# OSSILEDControllerNew.net
KiCad netlist of a schematic drawn in EAGLE
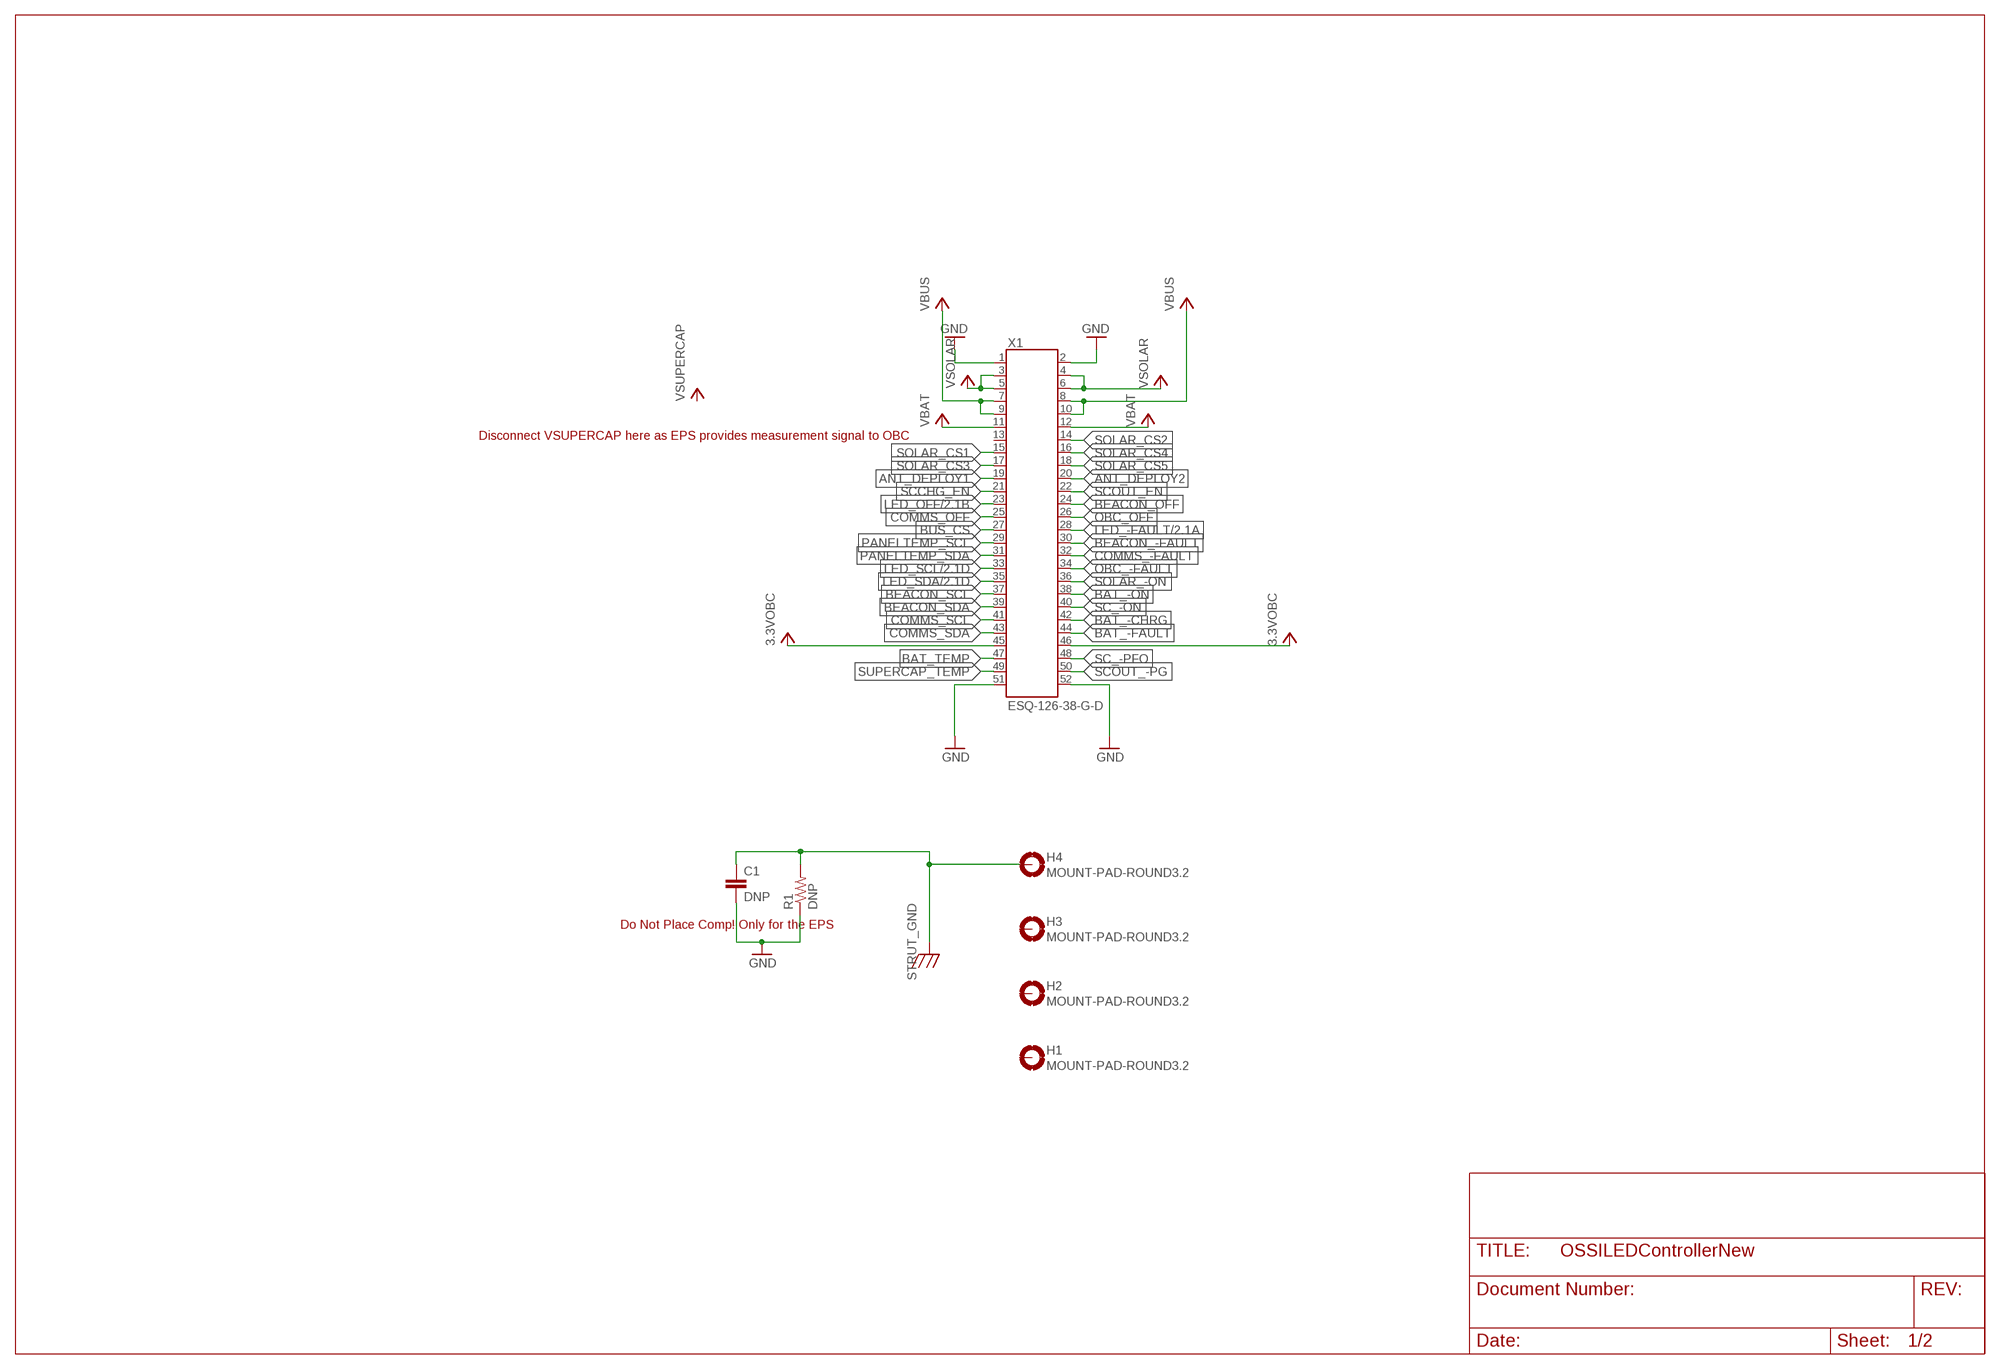
[diagram p0: schematic, sheet 1]
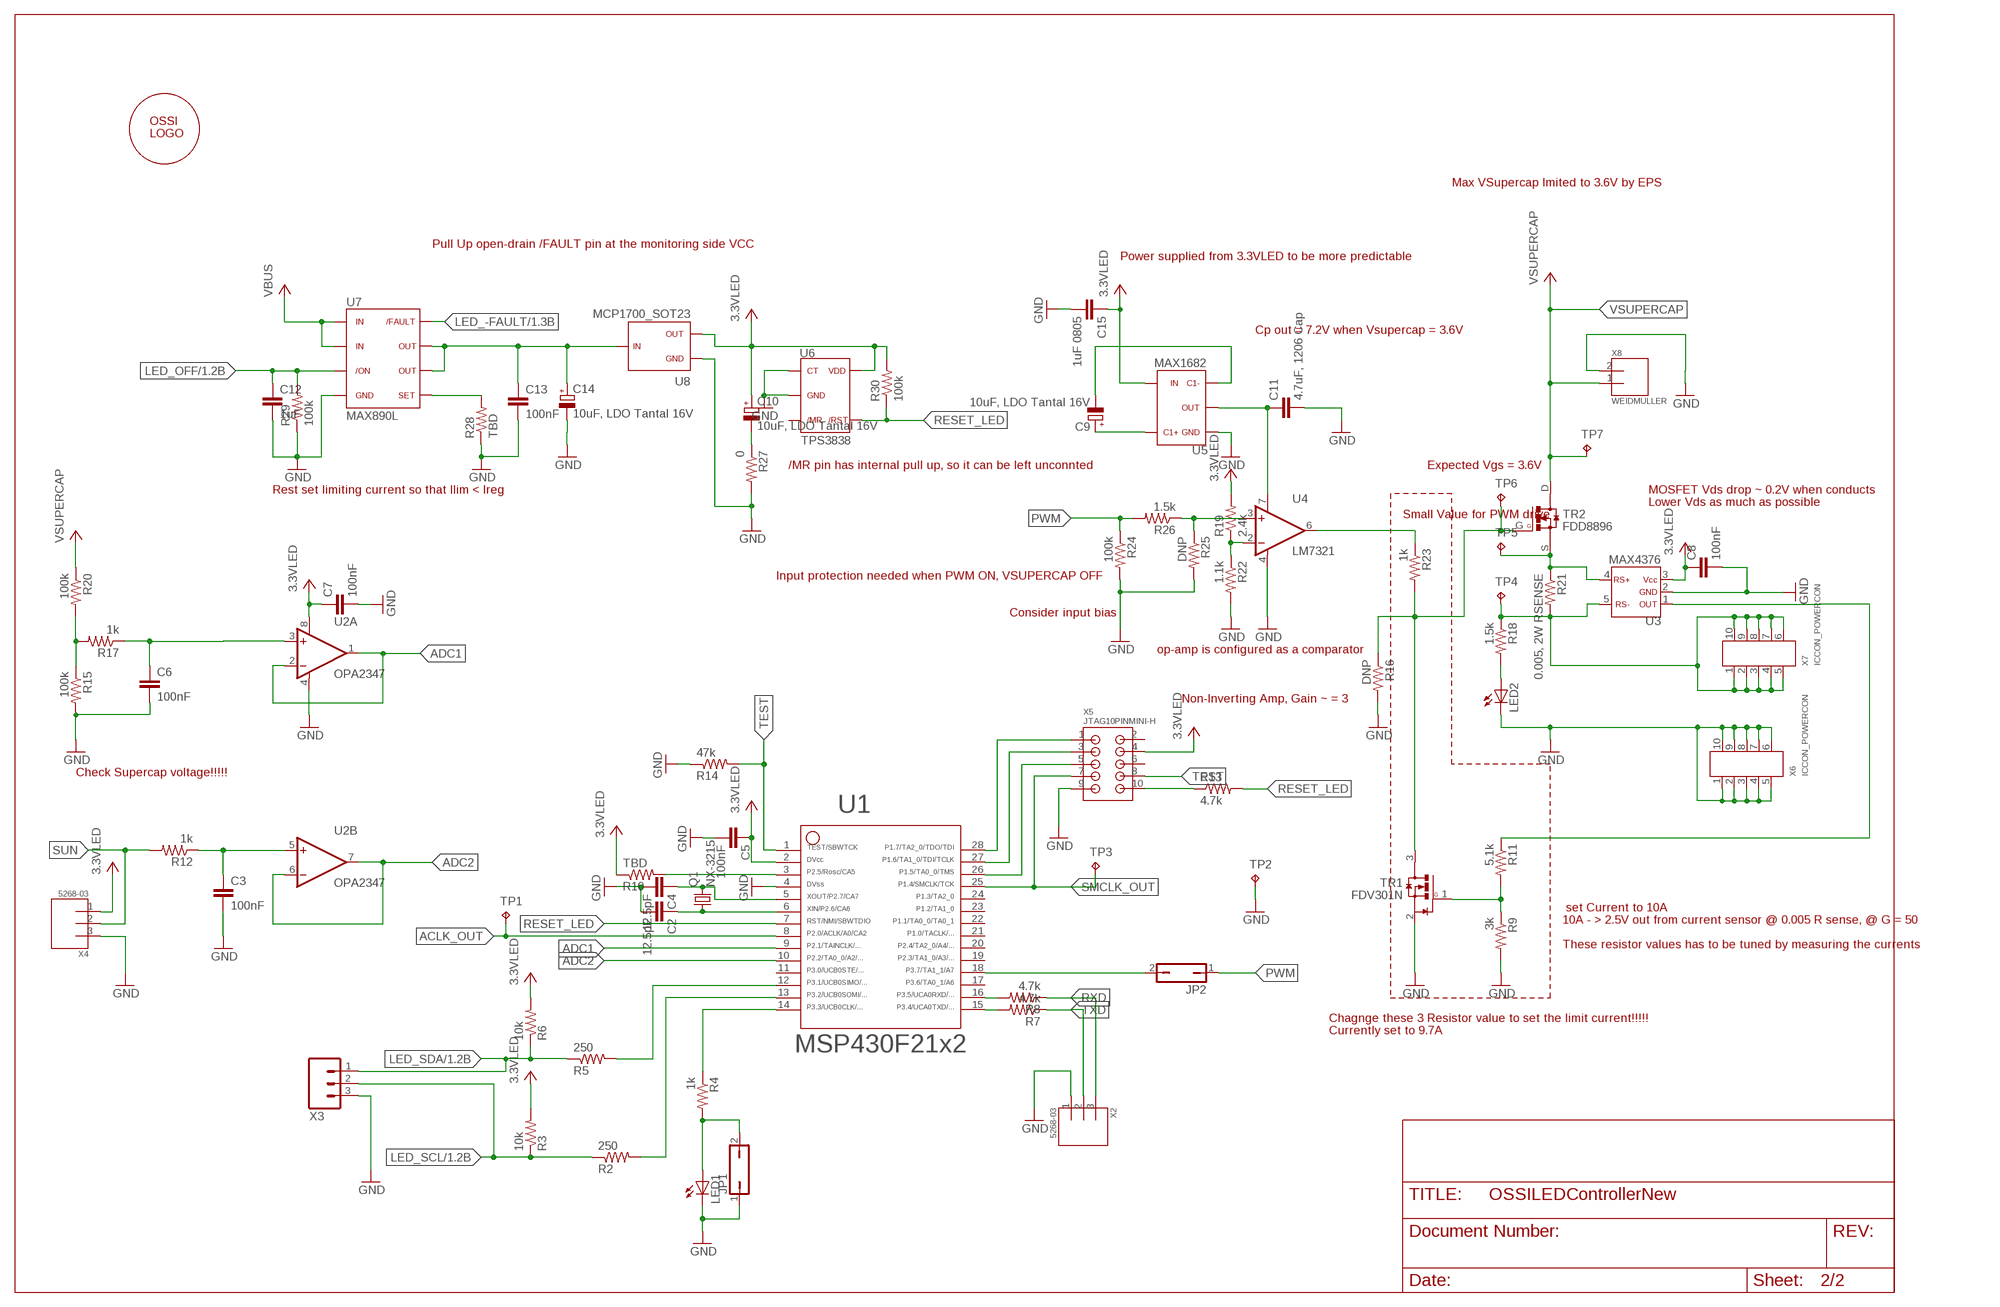
[diagram p1: schematic, sheet 2]

(export (version "E")
  (design (tool "Eeschema 10.0.6"))
  (components
    (comp (ref "C2")
      (value "12.5pF")
      (footprint "eagle-import:C0603(1608)")
      (libsource (lib "eagle-import") (part "C0603(1608)"))
    )
    (comp (ref "C3")
      (value "100nF")
      (footprint "eagle-import:C0603(1608)")
      (libsource (lib "eagle-import") (part "C0603(1608)"))
    )
    (comp (ref "C4")
      (value "12.5pF")
      (footprint "eagle-import:C0603(1608)")
      (libsource (lib "eagle-import") (part "C0603(1608)"))
    )
    (comp (ref "C5")
      (value "100nF")
      (footprint "eagle-import:C0603(1608)")
      (libsource (lib "eagle-import") (part "C0603(1608)"))
    )
    (comp (ref "C6")
      (value "100nF")
      (footprint "eagle-import:C0603(1608)")
      (libsource (lib "eagle-import") (part "C0603(1608)"))
    )
    (comp (ref "C7")
      (value "100nF")
      (footprint "eagle-import:C0603(1608)")
      (libsource (lib "eagle-import") (part "C0603(1608)"))
    )
    (comp (ref "C8")
      (value "100nF")
      (footprint "eagle-import:C0603(1608)")
      (libsource (lib "eagle-import") (part "C0603(1608)"))
    )
    (comp (ref "C9")
      (value "10uF, LDO Tantal 16V")
      (footprint "eagle-import:C1206(3216)-A")
      (libsource (lib "eagle-import") (part "C-TANTAL-A"))
    )
    (comp (ref "C10")
      (value "10uF, LDO Tantal 16V")
      (footprint "eagle-import:C1206(3216)-A")
      (libsource (lib "eagle-import") (part "C-TANTAL-A"))
    )
    (comp (ref "C11")
      (value "4.7uF, 1206 Cap")
      (footprint "eagle-import:C1206-GCM31")
      (libsource (lib "eagle-import") (part "C1206(3216)-GCM31"))
    )
    (comp (ref "C12")
      (value "1uF")
      (footprint "eagle-import:C0603(1608)")
      (libsource (lib "eagle-import") (part "C0603(1608)"))
    )
    (comp (ref "C13")
      (value "100nF")
      (footprint "eagle-import:C0603(1608)")
      (libsource (lib "eagle-import") (part "C0603(1608)"))
    )
    (comp (ref "C14")
      (value "10uF, LDO Tantal 16V")
      (footprint "eagle-import:C1206(3216)-A")
      (libsource (lib "eagle-import") (part "C-TANTAL-A"))
    )
    (comp (ref "C15")
      (value "1uF 0805")
      (footprint "eagle-import:C0805(2012)")
      (libsource (lib "eagle-import") (part "C0805(2012)"))
    )
    (comp (ref "JP1")
      (value "JP1Q")
      (footprint "eagle-import:JP1")
      (libsource (lib "eagle-import") (part "JP1Q"))
    )
    (comp (ref "JP2")
      (value "JP1Q")
      (footprint "eagle-import:JP1")
      (libsource (lib "eagle-import") (part "JP1Q"))
    )
    (comp (ref "LED1")
      (value "LED0603")
      (footprint "eagle-import:LED-0603")
      (libsource (lib "eagle-import") (part "LED0603"))
    )
    (comp (ref "LED2")
      (value "LEDCHIPLED_0603")
      (footprint "eagle-import:CHIPLED_0603")
      (libsource (lib "eagle-import") (part "LEDCHIPLED_0603"))
    )
    (comp (ref "Q1")
      (value "NX-3215")
      (footprint "eagle-import:NX-3215")
      (libsource (lib "eagle-import") (part "NX-3215"))
    )
    (comp (ref "R2")
      (value "250")
      (footprint "eagle-import:R0603(1608)")
      (libsource (lib "eagle-import") (part "R0603(1608)"))
    )
    (comp (ref "R3")
      (value "10k")
      (footprint "eagle-import:R0603(1608)")
      (libsource (lib "eagle-import") (part "R0603(1608)"))
    )
    (comp (ref "R4")
      (value "1k")
      (footprint "eagle-import:R0603(1608)")
      (libsource (lib "eagle-import") (part "R0603(1608)"))
    )
    (comp (ref "R5")
      (value "250")
      (footprint "eagle-import:R0603(1608)")
      (libsource (lib "eagle-import") (part "R0603(1608)"))
    )
    (comp (ref "R6")
      (value "10k")
      (footprint "eagle-import:R0603(1608)")
      (libsource (lib "eagle-import") (part "R0603(1608)"))
    )
    (comp (ref "R7")
      (value "4.7k")
      (footprint "eagle-import:R0603(1608)")
      (libsource (lib "eagle-import") (part "R0603(1608)"))
    )
    (comp (ref "R8")
      (value "4.7k")
      (footprint "eagle-import:R0603(1608)")
      (libsource (lib "eagle-import") (part "R0603(1608)"))
    )
    (comp (ref "R9")
      (value "3k")
      (footprint "eagle-import:R0603(1608)")
      (libsource (lib "eagle-import") (part "R0603(1608)"))
    )
    (comp (ref "R10")
      (value "TBD")
      (footprint "eagle-import:R0603(1608)")
      (libsource (lib "eagle-import") (part "R0603(1608)"))
    )
    (comp (ref "R11")
      (value "5.1k")
      (footprint "eagle-import:R0603(1608)")
      (libsource (lib "eagle-import") (part "R0603(1608)"))
    )
    (comp (ref "R12")
      (value "1k")
      (footprint "eagle-import:R0603(1608)")
      (libsource (lib "eagle-import") (part "R0603(1608)"))
    )
    (comp (ref "R13")
      (value "4.7k")
      (footprint "eagle-import:R0603(1608)")
      (libsource (lib "eagle-import") (part "R0603(1608)"))
    )
    (comp (ref "R14")
      (value "47k")
      (footprint "eagle-import:R0603(1608)")
      (libsource (lib "eagle-import") (part "R0603(1608)"))
    )
    (comp (ref "R15")
      (value "100k")
      (footprint "eagle-import:R0603(1608)")
      (libsource (lib "eagle-import") (part "R0603(1608)"))
    )
    (comp (ref "R16")
      (value "DNP")
      (footprint "eagle-import:R0603(1608)")
      (libsource (lib "eagle-import") (part "R0603(1608)"))
    )
    (comp (ref "R17")
      (value "1k")
      (footprint "eagle-import:R0603(1608)")
      (libsource (lib "eagle-import") (part "R0603(1608)"))
    )
    (comp (ref "R18")
      (value "1.5k")
      (footprint "eagle-import:R0603(1608)")
      (libsource (lib "eagle-import") (part "R0603(1608)"))
    )
    (comp (ref "R19")
      (value "2.4k")
      (footprint "eagle-import:R0603(1608)")
      (libsource (lib "eagle-import") (part "R0603(1608)"))
    )
    (comp (ref "R20")
      (value "100k")
      (footprint "eagle-import:R0603(1608)")
      (libsource (lib "eagle-import") (part "R0603(1608)"))
    )
    (comp (ref "R21")
      (value "0.005, 2W RSENSE")
      (footprint "eagle-import:R4527(12070)")
      (libsource (lib "eagle-import") (part "RWSR2"))
    )
    (comp (ref "R22")
      (value "1.1k")
      (footprint "eagle-import:R0603(1608)")
      (libsource (lib "eagle-import") (part "R0603(1608)"))
    )
    (comp (ref "R23")
      (value "1k")
      (footprint "eagle-import:R0603(1608)")
      (libsource (lib "eagle-import") (part "R0603(1608)"))
    )
    (comp (ref "R24")
      (value "100k")
      (footprint "eagle-import:R0603(1608)")
      (libsource (lib "eagle-import") (part "R0603(1608)"))
    )
    (comp (ref "R25")
      (value "DNP")
      (footprint "eagle-import:R0603(1608)")
      (libsource (lib "eagle-import") (part "R0603(1608)"))
    )
    (comp (ref "R26")
      (value "1.5k")
      (footprint "eagle-import:R0603(1608)")
      (libsource (lib "eagle-import") (part "R0603(1608)"))
    )
    (comp (ref "R27")
      (value "0")
      (footprint "eagle-import:R0603(1608)")
      (libsource (lib "eagle-import") (part "R0603(1608)"))
    )
    (comp (ref "R28")
      (value "TBD")
      (footprint "eagle-import:R0603(1608)")
      (libsource (lib "eagle-import") (part "R0603(1608)"))
    )
    (comp (ref "R29")
      (value "100k")
      (footprint "eagle-import:R0603(1608)")
      (libsource (lib "eagle-import") (part "R0603(1608)"))
    )
    (comp (ref "R30")
      (value "100k")
      (footprint "eagle-import:R0603(1608)")
      (libsource (lib "eagle-import") (part "R0603(1608)"))
    )
    (comp (ref "TP1")
      (value "TP")
      (footprint "eagle-import:TP-13")
      (libsource (lib "eagle-import") (part "TP"))
    )
    (comp (ref "TP2")
      (value "TP")
      (footprint "eagle-import:TP-13")
      (libsource (lib "eagle-import") (part "TP"))
    )
    (comp (ref "TP3")
      (value "TP")
      (footprint "eagle-import:TP-13")
      (libsource (lib "eagle-import") (part "TP"))
    )
    (comp (ref "TP4")
      (value "TP")
      (footprint "eagle-import:TP-13")
      (libsource (lib "eagle-import") (part "TP"))
    )
    (comp (ref "TP5")
      (value "TP")
      (footprint "eagle-import:TP-13")
      (libsource (lib "eagle-import") (part "TP"))
    )
    (comp (ref "TP6")
      (value "TP")
      (footprint "eagle-import:TP-13")
      (libsource (lib "eagle-import") (part "TP"))
    )
    (comp (ref "TP7")
      (value "TP")
      (footprint "eagle-import:TP-13")
      (libsource (lib "eagle-import") (part "TP"))
    )
    (comp (ref "TR1")
      (value "FDV301N")
      (footprint "eagle-import:SOT23")
      (libsource (lib "eagle-import") (part "FDV301N"))
    )
    (comp (ref "TR2")
      (value "FDD8896")
      (footprint "eagle-import:TO252")
      (libsource (lib "eagle-import") (part "FDD8896"))
    )
    (comp (ref "U$")
      (value "OSSILOGORECT")
      (footprint "eagle-import:OSSILOGORECT1005")
      (libsource (lib "eagle-import") (part "OSSILOGORECT"))
    )
    (comp (ref "U1")
      (value "MSP430F2132")
      (footprint "eagle-import:PW28")
      (libsource (lib "eagle-import") (part "MSP430F2132"))
    )
    (comp (ref "U2")
      (value "OPA2347")
      (footprint "eagle-import:SOT23-8DCN")
      (libsource (lib "eagle-import") (part "OPA2347"))
    )
    (comp (ref "U3")
      (value "MAX4376")
      (footprint "eagle-import:SOT23-5DBV")
      (libsource (lib "eagle-import") (part "MAX4376"))
    )
    (comp (ref "U4")
      (value "LM7321")
      (footprint "eagle-import:SO8")
      (libsource (lib "eagle-import") (part "LM7321"))
    )
    (comp (ref "U5")
      (value "MAX1682")
      (footprint "eagle-import:SOT23-5DBV")
      (libsource (lib "eagle-import") (part "MAX1682"))
    )
    (comp (ref "U6")
      (value "TPS3838")
      (footprint "eagle-import:SOT23-5DBV")
      (libsource (lib "eagle-import") (part "TPS3838"))
    )
    (comp (ref "U7")
      (value "MAX890L")
      (footprint "eagle-import:SO8")
      (libsource (lib "eagle-import") (part "MAX890L"))
    )
    (comp (ref "U8")
      (value "MCP1700_SOT23")
      (footprint "eagle-import:SOT23")
      (libsource (lib "eagle-import") (part "MCP1700_SOT23"))
    )
    (comp (ref "X2")
      (value "5268-03")
      (footprint "eagle-import:5268-03")
      (libsource (lib "eagle-import") (part "5268-03"))
    )
    (comp (ref "X3")
      (value "M03PTH")
      (footprint "eagle-import:1X03")
      (libsource (lib "eagle-import") (part "M03PTH"))
    )
    (comp (ref "X4")
      (value "5268-03")
      (footprint "eagle-import:5268-03")
      (libsource (lib "eagle-import") (part "5268-03"))
    )
    (comp (ref "X5")
      (value "JTAG10PINMINI-H")
      (footprint "eagle-import:M50-3200545")
      (libsource (lib "eagle-import") (part "JTAG10PINMINI-H"))
    )
    (comp (ref "X6")
      (value "ICCON_POWERCON")
      (footprint "eagle-import:ICCON6643220-1")
      (libsource (lib "eagle-import") (part "ICCON_POWERCON"))
    )
    (comp (ref "X7")
      (value "ICCON_POWERCON")
      (footprint "eagle-import:ICCON6643220-1")
      (libsource (lib "eagle-import") (part "ICCON_POWERCON"))
    )
    (comp (ref "X8")
      (value "WEIDMULLER")
      (footprint "eagle-import:WEIDMULLER1760490000")
      (libsource (lib "eagle-import") (part "WEIDMULLER"))
    )
    (comp (ref "C1")
      (value "DNP")
      (footprint "eagle-import:C0805(2012)")
      (libsource (lib "eagle-import") (part "C0805(2012)"))
    )
    (comp (ref "H1")
      (value "MOUNT-PAD-ROUND3.2")
      (footprint "eagle-import:3.2-PAD-ROUND")
      (libsource (lib "eagle-import") (part "MOUNT-PAD-ROUND3.2"))
    )
    (comp (ref "H2")
      (value "MOUNT-PAD-ROUND3.2")
      (footprint "eagle-import:3.2-PAD-ROUND")
      (libsource (lib "eagle-import") (part "MOUNT-PAD-ROUND3.2"))
    )
    (comp (ref "H3")
      (value "MOUNT-PAD-ROUND3.2")
      (footprint "eagle-import:3.2-PAD-ROUND")
      (libsource (lib "eagle-import") (part "MOUNT-PAD-ROUND3.2"))
    )
    (comp (ref "H4")
      (value "MOUNT-PAD-ROUND3.2")
      (footprint "eagle-import:3.2-PAD-ROUND")
      (libsource (lib "eagle-import") (part "MOUNT-PAD-ROUND3.2"))
    )
    (comp (ref "R1")
      (value "DNP")
      (footprint "eagle-import:WSL1206")
      (libsource (lib "eagle-import") (part "RWSL1206"))
    )
    (comp (ref "X1")
      (value "ESQ-126-38-G-D")
      (footprint "eagle-import:ESQ-126-XX-X-D")
      (libsource (lib "eagle-import") (part "ESQ-126-38-G-D"))
    )
  )
  (nets
    (net (code "1") (name "3.3VLED") (class "Default")
      (node (ref "C10") (pin "1") (pinfunction "+_1") (pintype "passive"))
      (node (ref "C15") (pin "1") (pinfunction "1_1") (pintype "passive"))
      (node (ref "C5") (pin "1") (pinfunction "1_1") (pintype "passive"))
      (node (ref "C7") (pin "1") (pinfunction "1_1") (pintype "passive"))
      (node (ref "C8") (pin "1") (pinfunction "1_1") (pintype "passive"))
      (node (ref "R10") (pin "1") (pinfunction "1_1") (pintype "passive"))
      (node (ref "R19") (pin "2") (pinfunction "2_2") (pintype "passive"))
      (node (ref "R3") (pin "2") (pinfunction "2_2") (pintype "passive"))
      (node (ref "R30") (pin "2") (pinfunction "2_2") (pintype "passive"))
      (node (ref "R6") (pin "2") (pinfunction "2_2") (pintype "passive"))
      (node (ref "U1") (pin "2") (pinfunction "2_2") (pintype "power_in"))
      (node (ref "U2") (pin "8") (pinfunction "V+_8") (pintype "power_in"))
      (node (ref "U3") (pin "3") (pinfunction "P$3_3") (pintype "power_in"))
      (node (ref "U5") (pin "4") (pinfunction "P$4_4") (pintype "power_in"))
      (node (ref "U6") (pin "5") (pinfunction "P$5_5") (pintype "power_in"))
      (node (ref "U8") (pin "2") (pinfunction "2_2") (pintype "power_in"))
      (node (ref "X4") (pin "1") (pinfunction "1_1") (pintype "bidirectional"))
      (node (ref "X5") (pin "4") (pinfunction "4_4") (pintype "bidirectional"))
    )
    (net (code "2") (name "3.3VOBC") (class "Default")
      (node (ref "X1") (pin "45") (pinfunction "45_45") (pintype "bidirectional"))
      (node (ref "X1") (pin "46") (pinfunction "46_46") (pintype "bidirectional"))
    )
    (net (code "3") (name "ACLK_OUT") (class "Default")
      (node (ref "TP1") (pin "TP") (pinfunction "TP_TP") (pintype "input"))
      (node (ref "U1") (pin "8") (pinfunction "8_8") (pintype "bidirectional"))
    )
    (net (code "4") (name "ADC1") (class "Default")
      (node (ref "U1") (pin "9") (pinfunction "9_9") (pintype "bidirectional"))
      (node (ref "U2") (pin "1") (pinfunction "OUT_1") (pintype "output"))
      (node (ref "U2") (pin "2") (pinfunction "-IN_2") (pintype "input"))
    )
    (net (code "5") (name "ADC2") (class "Default")
      (node (ref "U1") (pin "10") (pinfunction "10_10") (pintype "bidirectional"))
      (node (ref "U2") (pin "6") (pinfunction "-IN_6") (pintype "input"))
      (node (ref "U2") (pin "7") (pinfunction "OUT_7") (pintype "output"))
    )
    (net (code "6") (name "ANT_DEPLOY1") (class "Default")
      (node (ref "X1") (pin "19") (pinfunction "19_19") (pintype "bidirectional"))
    )
    (net (code "7") (name "ANT_DEPLOY2") (class "Default")
      (node (ref "X1") (pin "20") (pinfunction "20_20") (pintype "bidirectional"))
    )
    (net (code "8") (name "BAT_-CHRG") (class "Default")
      (node (ref "X1") (pin "42") (pinfunction "42_42") (pintype "bidirectional"))
    )
    (net (code "9") (name "BAT_-FAULT") (class "Default")
      (node (ref "X1") (pin "44") (pinfunction "44_44") (pintype "bidirectional"))
    )
    (net (code "10") (name "BAT_-ON") (class "Default")
      (node (ref "X1") (pin "38") (pinfunction "38_38") (pintype "bidirectional"))
    )
    (net (code "11") (name "BAT_TEMP") (class "Default")
      (node (ref "X1") (pin "47") (pinfunction "47_47") (pintype "bidirectional"))
    )
    (net (code "12") (name "BEACON_-FAULT") (class "Default")
      (node (ref "X1") (pin "30") (pinfunction "30_30") (pintype "bidirectional"))
    )
    (net (code "13") (name "BEACON_OFF") (class "Default")
      (node (ref "X1") (pin "24") (pinfunction "24_24") (pintype "bidirectional"))
    )
    (net (code "14") (name "BEACON_SCL") (class "Default")
      (node (ref "X1") (pin "37") (pinfunction "37_37") (pintype "bidirectional"))
    )
    (net (code "15") (name "BEACON_SDA") (class "Default")
      (node (ref "X1") (pin "39") (pinfunction "39_39") (pintype "bidirectional"))
    )
    (net (code "16") (name "BUS_CS") (class "Default")
      (node (ref "X1") (pin "27") (pinfunction "27_27") (pintype "bidirectional"))
    )
    (net (code "17") (name "COMMS_-FAULT") (class "Default")
      (node (ref "X1") (pin "32") (pinfunction "32_32") (pintype "bidirectional"))
    )
    (net (code "18") (name "COMMS_OFF") (class "Default")
      (node (ref "X1") (pin "25") (pinfunction "25_25") (pintype "bidirectional"))
    )
    (net (code "19") (name "COMMS_SCL") (class "Default")
      (node (ref "X1") (pin "41") (pinfunction "41_41") (pintype "bidirectional"))
    )
    (net (code "20") (name "COMMS_SDA") (class "Default")
      (node (ref "X1") (pin "43") (pinfunction "43_43") (pintype "bidirectional"))
    )
    (net (code "21") (name "GND") (class "Default")
      (node (ref "C1") (pin "2") (pinfunction "2_2") (pintype "passive"))
      (node (ref "C11") (pin "P$2") (pinfunction "2_P$2") (pintype "passive"))
      (node (ref "C12") (pin "2") (pinfunction "2_2") (pintype "passive"))
      (node (ref "C13") (pin "2") (pinfunction "2_2") (pintype "passive"))
      (node (ref "C14") (pin "2") (pinfunction "-_2") (pintype "passive"))
      (node (ref "C15") (pin "2") (pinfunction "2_2") (pintype "passive"))
      (node (ref "C2") (pin "2") (pinfunction "2_2") (pintype "passive"))
      (node (ref "C3") (pin "2") (pinfunction "2_2") (pintype "passive"))
      (node (ref "C4") (pin "2") (pinfunction "2_2") (pintype "passive"))
      (node (ref "C5") (pin "2") (pinfunction "2_2") (pintype "passive"))
      (node (ref "C6") (pin "2") (pinfunction "2_2") (pintype "passive"))
      (node (ref "C7") (pin "2") (pinfunction "2_2") (pintype "passive"))
      (node (ref "C8") (pin "2") (pinfunction "2_2") (pintype "passive"))
      (node (ref "JP1") (pin "1") (pinfunction "1_1") (pintype "passive"))
      (node (ref "LED1") (pin "C") (pinfunction "C_C") (pintype "passive"))
      (node (ref "LED2") (pin "C") (pinfunction "C_C") (pintype "passive"))
      (node (ref "R1") (pin "P$1") (pinfunction "1_P$1") (pintype "passive"))
      (node (ref "R14") (pin "1") (pinfunction "1_1") (pintype "passive"))
      (node (ref "R15") (pin "2") (pinfunction "2_2") (pintype "passive"))
      (node (ref "R16") (pin "2") (pinfunction "2_2") (pintype "passive"))
      (node (ref "R22") (pin "2") (pinfunction "2_2") (pintype "passive"))
      (node (ref "R24") (pin "2") (pinfunction "2_2") (pintype "passive"))
      (node (ref "R25") (pin "2") (pinfunction "2_2") (pintype "passive"))
      (node (ref "R27") (pin "2") (pinfunction "2_2") (pintype "passive"))
      (node (ref "R28") (pin "1") (pinfunction "1_1") (pintype "passive"))
      (node (ref "R29") (pin "1") (pinfunction "1_1") (pintype "passive"))
      (node (ref "R9") (pin "2") (pinfunction "2_2") (pintype "passive"))
      (node (ref "TP2") (pin "TP") (pinfunction "TP_TP") (pintype "input"))
      (node (ref "TR1") (pin "2") (pinfunction "S_2") (pintype "bidirectional"))
      (node (ref "U1") (pin "4") (pinfunction "4_4") (pintype "power_in"))
      (node (ref "U2") (pin "4") (pinfunction "V-_4") (pintype "power_in"))
      (node (ref "U3") (pin "2") (pinfunction "P$2_2") (pintype "power_in"))
      (node (ref "U4") (pin "4") (pinfunction "V-_4") (pintype "power_in"))
      (node (ref "U5") (pin "1") (pinfunction "P$1_1") (pintype "power_in"))
      (node (ref "U6") (pin "1") (pinfunction "P$1_1") (pintype "bidirectional"))
      (node (ref "U6") (pin "2") (pinfunction "P$2_2") (pintype "power_in"))
      (node (ref "U7") (pin "4") (pinfunction "P$4_4") (pintype "power_in"))
      (node (ref "U8") (pin "1") (pinfunction "1_1") (pintype "power_in"))
      (node (ref "X1") (pin "1") (pinfunction "1_1") (pintype "bidirectional"))
      (node (ref "X1") (pin "2") (pinfunction "2_2") (pintype "bidirectional"))
      (node (ref "X1") (pin "51") (pinfunction "51_51") (pintype "bidirectional"))
      (node (ref "X1") (pin "52") (pinfunction "52_52") (pintype "bidirectional"))
      (node (ref "X2") (pin "1") (pinfunction "1_1") (pintype "bidirectional"))
      (node (ref "X3") (pin "3") (pinfunction "3_3") (pintype "passive"))
      (node (ref "X4") (pin "3") (pinfunction "3_3") (pintype "bidirectional"))
      (node (ref "X5") (pin "9") (pinfunction "9_9") (pintype "bidirectional"))
      (node (ref "X6") (pin "1") (pinfunction "P$1_1") (pintype "bidirectional"))
      (node (ref "X6") (pin "10") (pinfunction "P$10_10") (pintype "bidirectional"))
      (node (ref "X6") (pin "2") (pinfunction "P$2_2") (pintype "bidirectional"))
      (node (ref "X6") (pin "3") (pinfunction "P$3_3") (pintype "bidirectional"))
      (node (ref "X6") (pin "4") (pinfunction "P$4_4") (pintype "bidirectional"))
      (node (ref "X6") (pin "5") (pinfunction "P$5_5") (pintype "bidirectional"))
      (node (ref "X6") (pin "6") (pinfunction "P$6_6") (pintype "bidirectional"))
      (node (ref "X6") (pin "7") (pinfunction "P$7_7") (pintype "bidirectional"))
      (node (ref "X6") (pin "8") (pinfunction "P$8_8") (pintype "bidirectional"))
      (node (ref "X6") (pin "9") (pinfunction "P$9_9") (pintype "bidirectional"))
      (node (ref "X8") (pin "2") (pinfunction "2_2") (pintype "bidirectional"))
    )
    (net (code "22") (name "LED_-FAULT") (class "Default")
      (node (ref "U7") (pin "8") (pinfunction "P$8_8") (pintype "output"))
      (node (ref "X1") (pin "28") (pinfunction "28_28") (pintype "bidirectional"))
    )
    (net (code "23") (name "LED_OFF") (class "Default")
      (node (ref "C12") (pin "1") (pinfunction "1_1") (pintype "passive"))
      (node (ref "R29") (pin "2") (pinfunction "2_2") (pintype "passive"))
      (node (ref "U7") (pin "3") (pinfunction "P$3_3") (pintype "input"))
      (node (ref "X1") (pin "23") (pinfunction "23_23") (pintype "bidirectional"))
    )
    (net (code "24") (name "LED_SCL") (class "Default")
      (node (ref "R2") (pin "1") (pinfunction "1_1") (pintype "passive"))
      (node (ref "R3") (pin "1") (pinfunction "1_1") (pintype "passive"))
      (node (ref "X1") (pin "33") (pinfunction "33_33") (pintype "bidirectional"))
      (node (ref "X3") (pin "2") (pinfunction "2_2") (pintype "passive"))
    )
    (net (code "25") (name "LED_SDA") (class "Default")
      (node (ref "R5") (pin "1") (pinfunction "1_1") (pintype "passive"))
      (node (ref "R6") (pin "1") (pinfunction "1_1") (pintype "passive"))
      (node (ref "X1") (pin "35") (pinfunction "35_35") (pintype "bidirectional"))
      (node (ref "X3") (pin "1") (pinfunction "1_1") (pintype "passive"))
    )
    (net (code "26") (name "Net-(C2-Pad1)") (class "Default")
      (node (ref "C2") (pin "1") (pinfunction "1_1") (pintype "passive"))
      (node (ref "Q1") (pin "1") (pinfunction "1_1") (pintype "passive"))
      (node (ref "U1") (pin "6") (pinfunction "6_6") (pintype "bidirectional"))
    )
    (net (code "27") (name "Net-(C4-Pad1)") (class "Default")
      (node (ref "C4") (pin "1") (pinfunction "1_1") (pintype "passive"))
      (node (ref "Q1") (pin "2") (pinfunction "2_2") (pintype "passive"))
      (node (ref "U1") (pin "5") (pinfunction "5_5") (pintype "bidirectional"))
    )
    (net (code "28") (name "Net-(C9-+)") (class "Default")
      (node (ref "C9") (pin "1") (pinfunction "+_1") (pintype "passive"))
      (node (ref "U5") (pin "5") (pinfunction "P$5_5") (pintype "passive"))
    )
    (net (code "29") (name "Net-(C9--)") (class "Default")
      (node (ref "C9") (pin "2") (pinfunction "-_2") (pintype "passive"))
      (node (ref "U5") (pin "3") (pinfunction "P$3_3") (pintype "passive"))
    )
    (net (code "30") (name "Net-(C10--)") (class "Default")
      (node (ref "C10") (pin "2") (pinfunction "-_2") (pintype "passive"))
      (node (ref "R27") (pin "1") (pinfunction "1_1") (pintype "passive"))
    )
    (net (code "31") (name "Net-(C11-1)") (class "Default")
      (node (ref "C11") (pin "P$1") (pinfunction "1_P$1") (pintype "passive"))
      (node (ref "U4") (pin "7") (pinfunction "V+_7") (pintype "power_in"))
      (node (ref "U5") (pin "2") (pinfunction "P$2_2") (pintype "power_in"))
    )
    (net (code "32") (name "Net-(C14-+)") (class "Default")
      (node (ref "C13") (pin "1") (pinfunction "1_1") (pintype "passive"))
      (node (ref "C14") (pin "1") (pinfunction "+_1") (pintype "passive"))
      (node (ref "U7") (pin "6") (pinfunction "P$6_6") (pintype "output"))
      (node (ref "U7") (pin "7") (pinfunction "P$7_7") (pintype "output"))
      (node (ref "U8") (pin "3") (pinfunction "3_3") (pintype "power_in"))
    )
    (net (code "33") (name "Net-(JP1-Pad2)") (class "Default")
      (node (ref "JP1") (pin "2") (pinfunction "2_2") (pintype "passive"))
      (node (ref "LED1") (pin "A") (pinfunction "A_A") (pintype "passive"))
      (node (ref "R4") (pin "2") (pinfunction "2_2") (pintype "passive"))
    )
    (net (code "34") (name "Net-(JP2-Pad2)") (class "Default")
      (node (ref "JP2") (pin "2") (pinfunction "2_2") (pintype "passive"))
      (node (ref "U1") (pin "18") (pinfunction "18_18") (pintype "bidirectional"))
    )
    (net (code "35") (name "Net-(LED2-PadA)") (class "Default")
      (node (ref "LED2") (pin "A") (pinfunction "A_A") (pintype "passive"))
      (node (ref "R18") (pin "2") (pinfunction "2_2") (pintype "passive"))
    )
    (net (code "36") (name "Net-(R2-Pad2)") (class "Default")
      (node (ref "R2") (pin "2") (pinfunction "2_2") (pintype "passive"))
      (node (ref "U1") (pin "13") (pinfunction "13_13") (pintype "bidirectional"))
    )
    (net (code "37") (name "Net-(R4-Pad1)") (class "Default")
      (node (ref "R4") (pin "1") (pinfunction "1_1") (pintype "passive"))
      (node (ref "U1") (pin "14") (pinfunction "14_14") (pintype "bidirectional"))
    )
    (net (code "38") (name "Net-(R5-Pad2)") (class "Default")
      (node (ref "R5") (pin "2") (pinfunction "2_2") (pintype "passive"))
      (node (ref "U1") (pin "12") (pinfunction "12_12") (pintype "bidirectional"))
    )
    (net (code "39") (name "Net-(R7-Pad2)") (class "Default")
      (node (ref "R7") (pin "2") (pinfunction "2_2") (pintype "passive"))
      (node (ref "U1") (pin "15") (pinfunction "15_15") (pintype "bidirectional"))
    )
    (net (code "40") (name "Net-(R8-Pad2)") (class "Default")
      (node (ref "R8") (pin "2") (pinfunction "2_2") (pintype "passive"))
      (node (ref "U1") (pin "16") (pinfunction "16_16") (pintype "bidirectional"))
    )
    (net (code "41") (name "Net-(R10-Pad2)") (class "Default")
      (node (ref "R10") (pin "2") (pinfunction "2_2") (pintype "passive"))
      (node (ref "U1") (pin "3") (pinfunction "3_3") (pintype "bidirectional"))
    )
    (net (code "42") (name "Net-(R13-Pad1)") (class "Default")
      (node (ref "R13") (pin "1") (pinfunction "1_1") (pintype "passive"))
      (node (ref "X5") (pin "10") (pinfunction "10_10") (pintype "bidirectional"))
    )
    (net (code "43") (name "Net-(R15-Pad1)") (class "Default")
      (node (ref "R15") (pin "1") (pinfunction "1_1") (pintype "passive"))
      (node (ref "R17") (pin "2") (pinfunction "2_2") (pintype "passive"))
      (node (ref "R20") (pin "2") (pinfunction "2_2") (pintype "passive"))
    )
    (net (code "44") (name "Net-(R21-1)") (class "Default")
      (node (ref "R21") (pin "P$1") (pinfunction "1_P$1") (pintype "passive"))
      (node (ref "TP5") (pin "TP") (pinfunction "TP_TP") (pintype "input"))
      (node (ref "TR2") (pin "S") (pinfunction "S_S") (pintype "bidirectional"))
      (node (ref "U3") (pin "4") (pinfunction "P$4_4") (pintype "input"))
    )
    (net (code "45") (name "Net-(R21-2)") (class "Default")
      (node (ref "R18") (pin "1") (pinfunction "1_1") (pintype "passive"))
      (node (ref "R21") (pin "P$2") (pinfunction "2_P$2") (pintype "passive"))
      (node (ref "TP4") (pin "TP") (pinfunction "TP_TP") (pintype "input"))
      (node (ref "U3") (pin "5") (pinfunction "P$5_5") (pintype "input"))
      (node (ref "X7") (pin "1") (pinfunction "P$1_1") (pintype "bidirectional"))
      (node (ref "X7") (pin "10") (pinfunction "P$10_10") (pintype "bidirectional"))
      (node (ref "X7") (pin "2") (pinfunction "P$2_2") (pintype "bidirectional"))
      (node (ref "X7") (pin "3") (pinfunction "P$3_3") (pintype "bidirectional"))
      (node (ref "X7") (pin "4") (pinfunction "P$4_4") (pintype "bidirectional"))
      (node (ref "X7") (pin "5") (pinfunction "P$5_5") (pintype "bidirectional"))
      (node (ref "X7") (pin "6") (pinfunction "P$6_6") (pintype "bidirectional"))
      (node (ref "X7") (pin "7") (pinfunction "P$7_7") (pintype "bidirectional"))
      (node (ref "X7") (pin "8") (pinfunction "P$8_8") (pintype "bidirectional"))
      (node (ref "X7") (pin "9") (pinfunction "P$9_9") (pintype "bidirectional"))
    )
    (net (code "46") (name "Net-(TR1-D)") (class "Default")
      (node (ref "R16") (pin "1") (pinfunction "1_1") (pintype "passive"))
      (node (ref "R23") (pin "2") (pinfunction "2_2") (pintype "passive"))
      (node (ref "TP6") (pin "TP") (pinfunction "TP_TP") (pintype "input"))
      (node (ref "TR1") (pin "3") (pinfunction "D_3") (pintype "bidirectional"))
      (node (ref "TR2") (pin "G") (pinfunction "G_G") (pintype "bidirectional"))
    )
    (net (code "47") (name "Net-(TR1-G)") (class "Default")
      (node (ref "R11") (pin "2") (pinfunction "2_2") (pintype "passive"))
      (node (ref "R9") (pin "1") (pinfunction "1_1") (pintype "passive"))
      (node (ref "TR1") (pin "1") (pinfunction "G_1") (pintype "bidirectional"))
    )
    (net (code "48") (name "Net-(U1-Pad26)") (class "Default")
      (node (ref "U1") (pin "26") (pinfunction "26_26") (pintype "bidirectional"))
      (node (ref "X5") (pin "5") (pinfunction "5_5") (pintype "bidirectional"))
    )
    (net (code "49") (name "Net-(U1-Pad27)") (class "Default")
      (node (ref "U1") (pin "27") (pinfunction "27_27") (pintype "bidirectional"))
      (node (ref "X5") (pin "3") (pinfunction "3_3") (pintype "bidirectional"))
    )
    (net (code "50") (name "Net-(U1-Pad28)") (class "Default")
      (node (ref "U1") (pin "28") (pinfunction "28_28") (pintype "bidirectional"))
      (node (ref "X5") (pin "1") (pinfunction "1_1") (pintype "bidirectional"))
    )
    (net (code "51") (name "Net-(U2A-+IN)") (class "Default")
      (node (ref "C6") (pin "1") (pinfunction "1_1") (pintype "passive"))
      (node (ref "R17") (pin "1") (pinfunction "1_1") (pintype "passive"))
      (node (ref "U2") (pin "3") (pinfunction "+IN_3") (pintype "input"))
    )
    (net (code "52") (name "Net-(U2B-+IN)") (class "Default")
      (node (ref "C3") (pin "1") (pinfunction "1_1") (pintype "passive"))
      (node (ref "R12") (pin "1") (pinfunction "1_1") (pintype "passive"))
      (node (ref "U2") (pin "5") (pinfunction "+IN_5") (pintype "input"))
    )
    (net (code "53") (name "Net-(U3-P$1)") (class "Default")
      (node (ref "R11") (pin "1") (pinfunction "1_1") (pintype "passive"))
      (node (ref "U3") (pin "1") (pinfunction "P$1_1") (pintype "output"))
    )
    (net (code "54") (name "Net-(U4-+IN)") (class "Default")
      (node (ref "R25") (pin "1") (pinfunction "1_1") (pintype "passive"))
      (node (ref "R26") (pin "1") (pinfunction "1_1") (pintype "passive"))
      (node (ref "U4") (pin "3") (pinfunction "+IN_3") (pintype "input"))
    )
    (net (code "55") (name "Net-(U4--IN)") (class "Default")
      (node (ref "R19") (pin "1") (pinfunction "1_1") (pintype "passive"))
      (node (ref "R22") (pin "1") (pinfunction "1_1") (pintype "passive"))
      (node (ref "U4") (pin "2") (pinfunction "-IN_2") (pintype "input"))
    )
    (net (code "56") (name "Net-(U4-OUT)") (class "Default")
      (node (ref "R23") (pin "1") (pinfunction "1_1") (pintype "passive"))
      (node (ref "U4") (pin "6") (pinfunction "OUT_6") (pintype "output"))
    )
    (net (code "57") (name "Net-(U7-P$5)") (class "Default")
      (node (ref "R28") (pin "2") (pinfunction "2_2") (pintype "passive"))
      (node (ref "U7") (pin "5") (pinfunction "P$5_5") (pintype "passive"))
    )
    (net (code "58") (name "OBC_-FAULT") (class "Default")
      (node (ref "X1") (pin "34") (pinfunction "34_34") (pintype "bidirectional"))
    )
    (net (code "59") (name "OBC_OFF") (class "Default")
      (node (ref "X1") (pin "26") (pinfunction "26_26") (pintype "bidirectional"))
    )
    (net (code "60") (name "PANELTEMP_SCL") (class "Default")
      (node (ref "X1") (pin "29") (pinfunction "29_29") (pintype "bidirectional"))
    )
    (net (code "61") (name "PANELTEMP_SDA") (class "Default")
      (node (ref "X1") (pin "31") (pinfunction "31_31") (pintype "bidirectional"))
    )
    (net (code "62") (name "PWM") (class "Default")
      (node (ref "JP2") (pin "1") (pinfunction "1_1") (pintype "passive"))
      (node (ref "R24") (pin "1") (pinfunction "1_1") (pintype "passive"))
      (node (ref "R26") (pin "2") (pinfunction "2_2") (pintype "passive"))
    )
    (net (code "63") (name "RESET_LED") (class "Default")
      (node (ref "R13") (pin "2") (pinfunction "2_2") (pintype "passive"))
      (node (ref "R30") (pin "1") (pinfunction "1_1") (pintype "passive"))
      (node (ref "U1") (pin "7") (pinfunction "7_7") (pintype "input"))
      (node (ref "U6") (pin "4") (pinfunction "P$4_4") (pintype "output"))
    )
    (net (code "64") (name "RXD") (class "Default")
      (node (ref "R8") (pin "1") (pinfunction "1_1") (pintype "passive"))
      (node (ref "X2") (pin "3") (pinfunction "3_3") (pintype "bidirectional"))
    )
    (net (code "65") (name "SCCHG_EN") (class "Default")
      (node (ref "X1") (pin "21") (pinfunction "21_21") (pintype "bidirectional"))
    )
    (net (code "66") (name "SCOUT_-PG") (class "Default")
      (node (ref "X1") (pin "50") (pinfunction "50_50") (pintype "bidirectional"))
    )
    (net (code "67") (name "SCOUT_EN") (class "Default")
      (node (ref "X1") (pin "22") (pinfunction "22_22") (pintype "bidirectional"))
    )
    (net (code "68") (name "SC_-ON") (class "Default")
      (node (ref "X1") (pin "40") (pinfunction "40_40") (pintype "bidirectional"))
    )
    (net (code "69") (name "SC_-PFO") (class "Default")
      (node (ref "X1") (pin "48") (pinfunction "48_48") (pintype "bidirectional"))
    )
    (net (code "70") (name "SMCLK_OUT") (class "Default")
      (node (ref "TP3") (pin "TP") (pinfunction "TP_TP") (pintype "input"))
      (node (ref "U1") (pin "25") (pinfunction "25_25") (pintype "bidirectional"))
      (node (ref "X5") (pin "7") (pinfunction "7_7") (pintype "bidirectional"))
    )
    (net (code "71") (name "SOLAR_-ON") (class "Default")
      (node (ref "X1") (pin "36") (pinfunction "36_36") (pintype "bidirectional"))
    )
    (net (code "72") (name "SOLAR_CS1") (class "Default")
      (node (ref "X1") (pin "15") (pinfunction "15_15") (pintype "bidirectional"))
    )
    (net (code "73") (name "SOLAR_CS2") (class "Default")
      (node (ref "X1") (pin "14") (pinfunction "14_14") (pintype "bidirectional"))
    )
    (net (code "74") (name "SOLAR_CS3") (class "Default")
      (node (ref "X1") (pin "17") (pinfunction "17_17") (pintype "bidirectional"))
    )
    (net (code "75") (name "SOLAR_CS4") (class "Default")
      (node (ref "X1") (pin "16") (pinfunction "16_16") (pintype "bidirectional"))
    )
    (net (code "76") (name "SOLAR_CS5") (class "Default")
      (node (ref "X1") (pin "18") (pinfunction "18_18") (pintype "bidirectional"))
    )
    (net (code "77") (name "STRUT_GND") (class "Default")
      (node (ref "C1") (pin "1") (pinfunction "1_1") (pintype "passive"))
      (node (ref "H4") (pin "B3,2") (pinfunction "MOUNT_B3,2") (pintype "passive"))
      (node (ref "R1") (pin "P$2") (pinfunction "2_P$2") (pintype "passive"))
    )
    (net (code "78") (name "SUN") (class "Default")
      (node (ref "R12") (pin "2") (pinfunction "2_2") (pintype "passive"))
      (node (ref "X4") (pin "2") (pinfunction "2_2") (pintype "bidirectional"))
    )
    (net (code "79") (name "SUPERCAP_TEMP") (class "Default")
      (node (ref "X1") (pin "49") (pinfunction "49_49") (pintype "bidirectional"))
    )
    (net (code "80") (name "TEST") (class "Default")
      (node (ref "R14") (pin "2") (pinfunction "2_2") (pintype "passive"))
      (node (ref "U1") (pin "1") (pinfunction "1_1") (pintype "input"))
      (node (ref "X5") (pin "8") (pinfunction "8_8") (pintype "bidirectional"))
    )
    (net (code "81") (name "TXD") (class "Default")
      (node (ref "R7") (pin "1") (pinfunction "1_1") (pintype "passive"))
      (node (ref "X2") (pin "2") (pinfunction "2_2") (pintype "bidirectional"))
    )
    (net (code "82") (name "VBAT") (class "Default")
      (node (ref "X1") (pin "11") (pinfunction "11_11") (pintype "bidirectional"))
      (node (ref "X1") (pin "12") (pinfunction "12_12") (pintype "bidirectional"))
    )
    (net (code "83") (name "VBUS") (class "Default")
      (node (ref "U7") (pin "1") (pinfunction "P$1_1") (pintype "input"))
      (node (ref "U7") (pin "2") (pinfunction "P$2_2") (pintype "input"))
      (node (ref "X1") (pin "10") (pinfunction "10_10") (pintype "bidirectional"))
      (node (ref "X1") (pin "7") (pinfunction "7_7") (pintype "bidirectional"))
      (node (ref "X1") (pin "8") (pinfunction "8_8") (pintype "bidirectional"))
      (node (ref "X1") (pin "9") (pinfunction "9_9") (pintype "bidirectional"))
    )
    (net (code "84") (name "VSOLAR") (class "Default")
      (node (ref "X1") (pin "3") (pinfunction "3_3") (pintype "bidirectional"))
      (node (ref "X1") (pin "4") (pinfunction "4_4") (pintype "bidirectional"))
      (node (ref "X1") (pin "5") (pinfunction "5_5") (pintype "bidirectional"))
      (node (ref "X1") (pin "6") (pinfunction "6_6") (pintype "bidirectional"))
    )
    (net (code "85") (name "VSUPERCAP") (class "Default")
      (node (ref "R20") (pin "1") (pinfunction "1_1") (pintype "passive"))
      (node (ref "TP7") (pin "TP") (pinfunction "TP_TP") (pintype "input"))
      (node (ref "TR2") (pin "D") (pinfunction "D_D") (pintype "bidirectional"))
      (node (ref "X8") (pin "1") (pinfunction "1_1") (pintype "bidirectional"))
    )
    (net (code "86") (name "unconnected-(H1-MOUNT-PadB3,2)") (class "Default")
      (node (ref "H1") (pin "B3,2") (pinfunction "MOUNT_B3,2") (pintype "passive"))
    )
    (net (code "87") (name "unconnected-(H2-MOUNT-PadB3,2)") (class "Default")
      (node (ref "H2") (pin "B3,2") (pinfunction "MOUNT_B3,2") (pintype "passive"))
    )
    (net (code "88") (name "unconnected-(H3-MOUNT-PadB3,2)") (class "Default")
      (node (ref "H3") (pin "B3,2") (pinfunction "MOUNT_B3,2") (pintype "passive"))
    )
    (net (code "89") (name "unconnected-(U1-Pad11)") (class "Default")
      (node (ref "U1") (pin "11") (pinfunction "11_11") (pintype "bidirectional"))
    )
    (net (code "90") (name "unconnected-(U1-Pad17)") (class "Default")
      (node (ref "U1") (pin "17") (pinfunction "17_17") (pintype "bidirectional"))
    )
    (net (code "91") (name "unconnected-(U1-Pad19)") (class "Default")
      (node (ref "U1") (pin "19") (pinfunction "19_19") (pintype "bidirectional"))
    )
    (net (code "92") (name "unconnected-(U1-Pad20)") (class "Default")
      (node (ref "U1") (pin "20") (pinfunction "20_20") (pintype "bidirectional"))
    )
    (net (code "93") (name "unconnected-(U1-Pad21)") (class "Default")
      (node (ref "U1") (pin "21") (pinfunction "21_21") (pintype "bidirectional"))
    )
    (net (code "94") (name "unconnected-(U1-Pad22)") (class "Default")
      (node (ref "U1") (pin "22") (pinfunction "22_22") (pintype "bidirectional"))
    )
    (net (code "95") (name "unconnected-(U1-Pad23)") (class "Default")
      (node (ref "U1") (pin "23") (pinfunction "23_23") (pintype "bidirectional"))
    )
    (net (code "96") (name "unconnected-(U1-Pad24)") (class "Default")
      (node (ref "U1") (pin "24") (pinfunction "24_24") (pintype "bidirectional"))
    )
    (net (code "97") (name "unconnected-(U6-P$3-Pad3)") (class "Default")
      (node (ref "U6") (pin "3") (pinfunction "P$3_3") (pintype "input"))
    )
    (net (code "98") (name "unconnected-(X1-Pad13)") (class "Default")
      (node (ref "X1") (pin "13") (pinfunction "13_13") (pintype "bidirectional"))
    )
    (net (code "99") (name "unconnected-(X5-Pad2)") (class "Default")
      (node (ref "X5") (pin "2") (pinfunction "2_2") (pintype "bidirectional"))
    )
    (net (code "100") (name "unconnected-(X5-Pad6)") (class "Default")
      (node (ref "X5") (pin "6") (pinfunction "6_6") (pintype "bidirectional"))
    )
  )
)
